# Magnetorquer_Board.net
KiCad netlist of a schematic drawn in EAGLE
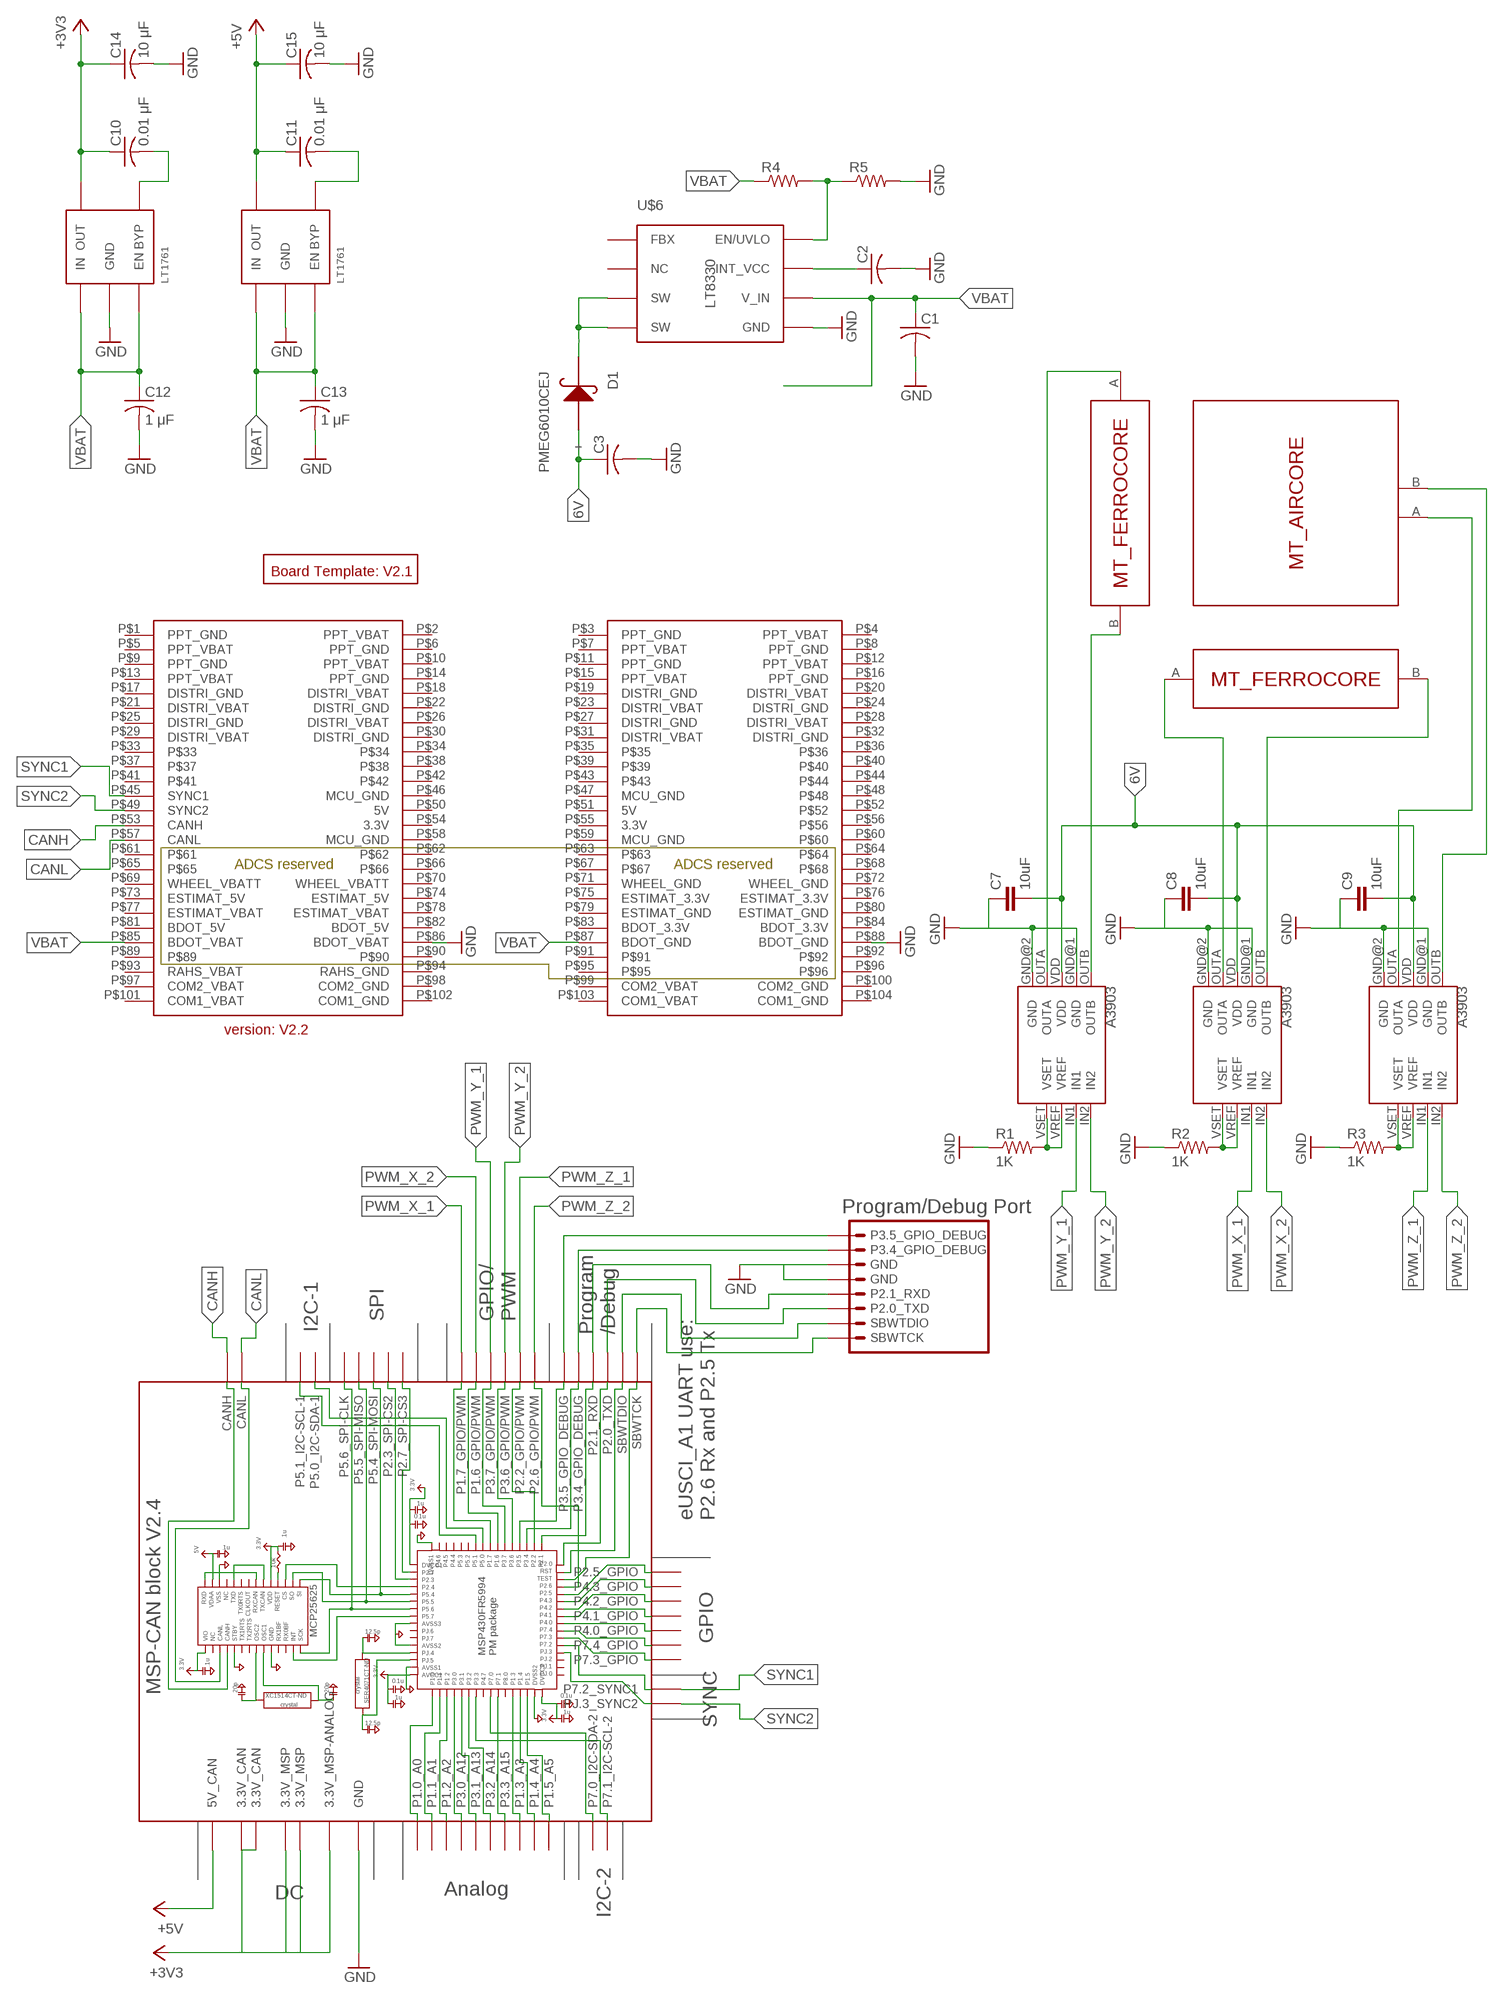
[diagram p0: schematic, sheet 1]

(export (version "E")
  (design (tool "Eeschema 10.0.6"))
  (components
    (comp (ref "C1")
      (value "C-USC0805")
      (footprint "eagle-import:C0805")
      (libsource (lib "eagle-import") (part "C-USC0805"))
    )
    (comp (ref "C2")
      (value "C-USC0805")
      (footprint "eagle-import:C0805")
      (libsource (lib "eagle-import") (part "C-USC0805"))
    )
    (comp (ref "C3")
      (value "C-USC0805")
      (footprint "eagle-import:C0805")
      (libsource (lib "eagle-import") (part "C-USC0805"))
    )
    (comp (ref "C7")
      (value "10uF")
      (footprint "eagle-import:C0805")
      (libsource (lib "eagle-import") (part "C-EUC0805"))
    )
    (comp (ref "C8")
      (value "10uF")
      (footprint "eagle-import:C0805")
      (libsource (lib "eagle-import") (part "C-EUC0805"))
    )
    (comp (ref "C9")
      (value "10uF")
      (footprint "eagle-import:C0805")
      (libsource (lib "eagle-import") (part "C-EUC0805"))
    )
    (comp (ref "C10")
      (value "0.01 μF")
      (footprint "eagle-import:C0805")
      (libsource (lib "eagle-import") (part "C-USC0805"))
    )
    (comp (ref "C11")
      (value "0.01 μF")
      (footprint "eagle-import:C0805")
      (libsource (lib "eagle-import") (part "C-USC0805"))
    )
    (comp (ref "C12")
      (value "1 μF")
      (footprint "eagle-import:C0805")
      (libsource (lib "eagle-import") (part "C-USC0805"))
    )
    (comp (ref "C13")
      (value "1 μF")
      (footprint "eagle-import:C0805")
      (libsource (lib "eagle-import") (part "C-USC0805"))
    )
    (comp (ref "C14")
      (value "10 μF")
      (footprint "eagle-import:C0805")
      (libsource (lib "eagle-import") (part "C-USC0805"))
    )
    (comp (ref "C15")
      (value "10 μF")
      (footprint "eagle-import:C0805")
      (libsource (lib "eagle-import") (part "C-USC0805"))
    )
    (comp (ref "D1")
      (value "PMEG6010CEJ")
      (footprint "eagle-import:SC-90")
      (libsource (lib "eagle-import") (part "PMEG6010CEJ"))
    )
    (comp (ref "LDO_3V3")
      (value "LINEAR_LDO_LT1761-X")
      (footprint "eagle-import:SOT-23-5")
      (libsource (lib "eagle-import") (part "LINEAR_LDO_LT1761-X"))
    )
    (comp (ref "LDO_5V")
      (value "LINEAR_LDO_LT1761-X")
      (footprint "eagle-import:SOT-23-5")
      (libsource (lib "eagle-import") (part "LINEAR_LDO_LT1761-X"))
    )
    (comp (ref "R1")
      (value "1K")
      (footprint "eagle-import:R0603")
      (libsource (lib "eagle-import") (part "R-US_R0603"))
    )
    (comp (ref "R2")
      (value "1K")
      (footprint "eagle-import:R0603")
      (libsource (lib "eagle-import") (part "R-US_R0603"))
    )
    (comp (ref "R3")
      (value "1K")
      (footprint "eagle-import:R0603")
      (libsource (lib "eagle-import") (part "R-US_R0603"))
    )
    (comp (ref "R4")
      (value "R-US_R0805")
      (footprint "eagle-import:R0805")
      (libsource (lib "eagle-import") (part "R-US_R0805"))
    )
    (comp (ref "R5")
      (value "R-US_R0805")
      (footprint "eagle-import:R0805")
      (libsource (lib "eagle-import") (part "R-US_R0805"))
    )
    (comp (ref "U$1")
      (value "PC104_CONNECTOR")
      (footprint "eagle-import:PC104_CONNECTOR")
      (libsource (lib "eagle-import") (part "PC104_CONNECTOR"))
    )
    (comp (ref "U$2")
      (value "BOARD_TEMPLATE")
      (footprint "eagle-import:BOARD_TEMPLATE")
      (libsource (lib "eagle-import") (part "BOARD_TEMPLATE"))
    )
    (comp (ref "U$3")
      (value "MT_AIRCORE")
      (footprint "eagle-import:MT_AIRCORE")
      (libsource (lib "eagle-import") (part "MT_AIRCORE"))
    )
    (comp (ref "U$4")
      (value "MT_FERROCORE")
      (footprint "eagle-import:MT_FERROCORE")
      (libsource (lib "eagle-import") (part "MT_FERROCORE"))
    )
    (comp (ref "U$5")
      (value "MT_FERROCORE")
      (footprint "eagle-import:MT_FERROCORE")
      (libsource (lib "eagle-import") (part "MT_FERROCORE"))
    )
    (comp (ref "U$6")
      (value "LT8330")
      (footprint "eagle-import:DDB")
      (libsource (lib "eagle-import") (part "LT8330"))
    )
    (comp (ref "U$7")
      (value "MSP-CAN_BLOCK")
      (footprint "eagle-import:MSP-CAN_BLOCK")
      (libsource (lib "eagle-import") (part "MSP-CAN_BLOCK"))
    )
    (comp (ref "U$8")
      (value "PROGRAM/DEBUG_PORT")
      (footprint "eagle-import:1X08_CONNECTOR")
      (libsource (lib "eagle-import") (part "PROGRAM/DEBUG_PORT"))
    )
    (comp (ref "U1")
      (value "A3903")
      (footprint "eagle-import:DFN-8EE")
      (libsource (lib "eagle-import") (part "A3903"))
    )
    (comp (ref "U2")
      (value "A3903")
      (footprint "eagle-import:DFN-8EE")
      (libsource (lib "eagle-import") (part "A3903"))
    )
    (comp (ref "U3")
      (value "A3903")
      (footprint "eagle-import:DFN-8EE")
      (libsource (lib "eagle-import") (part "A3903"))
    )
  )
  (nets
    (net (code "1") (name "+3V3") (class "Default")
      (node (ref "C10") (pin "1") (pinfunction "1_1") (pintype "passive"))
      (node (ref "C14") (pin "1") (pinfunction "1_1") (pintype "passive"))
      (node (ref "LDO_3V3") (pin "P$5") (pinfunction "OUT_P$5") (pintype "bidirectional"))
      (node (ref "U$7") (pin "3.3V@CAN1") (pinfunction "3.3V_CAN_3.3V@CAN1") (pintype "bidirectional"))
      (node (ref "U$7") (pin "3.3V@CAN2") (pinfunction "3.3V_CAN_3.3V@CAN2") (pintype "bidirectional"))
      (node (ref "U$7") (pin "3.3V@MSP1") (pinfunction "3.3V_MSP_3.3V@MSP1") (pintype "bidirectional"))
      (node (ref "U$7") (pin "3.3V@MSP2") (pinfunction "3.3V_MSP_3.3V@MSP2") (pintype "bidirectional"))
      (node (ref "U$7") (pin "3.3V_ANALOG@MSP2") (pinfunction "3.3V_MSP-ANALOG_3.3V_ANALOG@MSP2") (pintype "bidirectional"))
    )
    (net (code "2") (name "+5V") (class "Default")
      (node (ref "C11") (pin "1") (pinfunction "1_1") (pintype "passive"))
      (node (ref "C15") (pin "1") (pinfunction "1_1") (pintype "passive"))
      (node (ref "LDO_5V") (pin "P$5") (pinfunction "OUT_P$5") (pintype "bidirectional"))
      (node (ref "U$7") (pin "5V") (pinfunction "5V_CAN_5V") (pintype "bidirectional"))
    )
    (net (code "3") (name "6V") (class "Default")
      (node (ref "C3") (pin "1") (pinfunction "1_1") (pintype "passive"))
      (node (ref "C7") (pin "2") (pinfunction "2_2") (pintype "passive"))
      (node (ref "C8") (pin "2") (pinfunction "2_2") (pintype "passive"))
      (node (ref "C9") (pin "2") (pinfunction "2_2") (pintype "passive"))
      (node (ref "D1") (pin "P$1") (pinfunction "+_P$1") (pintype "bidirectional"))
      (node (ref "U1") (pin "VDD") (pinfunction "VDD_VDD") (pintype "power_in"))
      (node (ref "U2") (pin "VDD") (pinfunction "VDD_VDD") (pintype "power_in"))
      (node (ref "U3") (pin "VDD") (pinfunction "VDD_VDD") (pintype "power_in"))
    )
    (net (code "4") (name "CANH") (class "Default")
      (node (ref "U$1") (pin "P$53") (pinfunction "CANH_P$53") (pintype "bidirectional"))
      (node (ref "U$7") (pin "CANH") (pinfunction "CANH_CANH") (pintype "bidirectional"))
    )
    (net (code "5") (name "CANL") (class "Default")
      (node (ref "U$1") (pin "P$57") (pinfunction "CANL_P$57") (pintype "bidirectional"))
      (node (ref "U$7") (pin "CANL") (pinfunction "CANL_CANL") (pintype "bidirectional"))
    )
    (net (code "6") (name "GND") (class "Default")
      (node (ref "C1") (pin "2") (pinfunction "2_2") (pintype "passive"))
      (node (ref "C12") (pin "2") (pinfunction "2_2") (pintype "passive"))
      (node (ref "C13") (pin "2") (pinfunction "2_2") (pintype "passive"))
      (node (ref "C14") (pin "2") (pinfunction "2_2") (pintype "passive"))
      (node (ref "C15") (pin "2") (pinfunction "2_2") (pintype "passive"))
      (node (ref "C2") (pin "2") (pinfunction "2_2") (pintype "passive"))
      (node (ref "C3") (pin "2") (pinfunction "2_2") (pintype "passive"))
      (node (ref "C7") (pin "1") (pinfunction "1_1") (pintype "passive"))
      (node (ref "C8") (pin "1") (pinfunction "1_1") (pintype "passive"))
      (node (ref "C9") (pin "1") (pinfunction "1_1") (pintype "passive"))
      (node (ref "LDO_3V3") (pin "P$2") (pinfunction "GND_P$2") (pintype "bidirectional"))
      (node (ref "LDO_5V") (pin "P$2") (pinfunction "GND_P$2") (pintype "bidirectional"))
      (node (ref "R1") (pin "1") (pinfunction "1_1") (pintype "passive"))
      (node (ref "R2") (pin "1") (pinfunction "1_1") (pintype "passive"))
      (node (ref "R3") (pin "1") (pinfunction "1_1") (pintype "passive"))
      (node (ref "R5") (pin "2") (pinfunction "2_2") (pintype "passive"))
      (node (ref "U$1") (pin "P$86") (pinfunction "BDOT_VBAT_P$86") (pintype "bidirectional"))
      (node (ref "U$1") (pin "P$88") (pinfunction "BDOT_GND_P$88") (pintype "bidirectional"))
      (node (ref "U$6") (pin "GND") (pinfunction "GND_GND") (pintype "bidirectional"))
      (node (ref "U$6") (pin "P$5") (pinfunction "GND_P$5") (pintype "bidirectional"))
      (node (ref "U$7") (pin "GND@1") (pinfunction "GND_GND@1") (pintype "bidirectional"))
      (node (ref "U$7") (pin "GND@10") (pinfunction "GND_GND@10") (pintype "bidirectional"))
      (node (ref "U$7") (pin "GND@11") (pinfunction "GND_GND@11") (pintype "bidirectional"))
      (node (ref "U$7") (pin "GND@12") (pinfunction "GND_GND@12") (pintype "bidirectional"))
      (node (ref "U$7") (pin "GND@13") (pinfunction "GND_GND@13") (pintype "bidirectional"))
      (node (ref "U$7") (pin "GND@14") (pinfunction "GND_GND@14") (pintype "bidirectional"))
      (node (ref "U$7") (pin "GND@15") (pinfunction "GND_GND@15") (pintype "bidirectional"))
      (node (ref "U$7") (pin "GND@16") (pinfunction "GND_GND@16") (pintype "bidirectional"))
      (node (ref "U$7") (pin "GND@17") (pinfunction "GND_GND@17") (pintype "bidirectional"))
      (node (ref "U$7") (pin "GND@2") (pinfunction "GND_GND@2") (pintype "bidirectional"))
      (node (ref "U$7") (pin "GND@26") (pinfunction "GND_GND@26") (pintype "bidirectional"))
      (node (ref "U$7") (pin "GND@3") (pinfunction "GND_GND@3") (pintype "bidirectional"))
      (node (ref "U$7") (pin "GND@4") (pinfunction "GND_GND@4") (pintype "bidirectional"))
      (node (ref "U$7") (pin "GND@5") (pinfunction "GND_GND@5") (pintype "bidirectional"))
      (node (ref "U$7") (pin "GND@7") (pinfunction "GND_GND@7") (pintype "bidirectional"))
      (node (ref "U$7") (pin "GND@8") (pinfunction "GND_GND@8") (pintype "bidirectional"))
      (node (ref "U$7") (pin "GND@9") (pinfunction "GND_GND@9") (pintype "bidirectional"))
      (node (ref "U$8") (pin "5") (pinfunction "GND_5") (pintype "bidirectional"))
      (node (ref "U$8") (pin "6") (pinfunction "GND_6") (pintype "bidirectional"))
      (node (ref "U1") (pin "GND@1") (pinfunction "GND_GND@1") (pintype "power_in"))
      (node (ref "U1") (pin "GND@2") (pinfunction "GND_GND@2") (pintype "power_in"))
      (node (ref "U2") (pin "GND@1") (pinfunction "GND_GND@1") (pintype "power_in"))
      (node (ref "U2") (pin "GND@2") (pinfunction "GND_GND@2") (pintype "power_in"))
      (node (ref "U3") (pin "GND@1") (pinfunction "GND_GND@1") (pintype "power_in"))
      (node (ref "U3") (pin "GND@2") (pinfunction "GND_GND@2") (pintype "power_in"))
    )
    (net (code "7") (name "Net-(D1--)") (class "Default")
      (node (ref "D1") (pin "P$2") (pinfunction "-_P$2") (pintype "bidirectional"))
      (node (ref "U$6") (pin "P$3") (pinfunction "SW_P$3") (pintype "bidirectional"))
      (node (ref "U$6") (pin "P$4") (pinfunction "SW_P$4") (pintype "bidirectional"))
    )
    (net (code "8") (name "Net-(LDO_3V3-BYP)") (class "Default")
      (node (ref "C10") (pin "2") (pinfunction "2_2") (pintype "passive"))
      (node (ref "LDO_3V3") (pin "P$4") (pinfunction "BYP_P$4") (pintype "bidirectional"))
    )
    (net (code "9") (name "Net-(LDO_5V-BYP)") (class "Default")
      (node (ref "C11") (pin "2") (pinfunction "2_2") (pintype "passive"))
      (node (ref "LDO_5V") (pin "P$4") (pinfunction "BYP_P$4") (pintype "bidirectional"))
    )
    (net (code "10") (name "Net-(R1-Pad2)") (class "Default")
      (node (ref "R1") (pin "2") (pinfunction "2_2") (pintype "passive"))
      (node (ref "U1") (pin "VREF") (pinfunction "VREF_VREF") (pintype "power_in"))
      (node (ref "U1") (pin "VSET") (pinfunction "VSET_VSET") (pintype "bidirectional"))
    )
    (net (code "11") (name "Net-(R2-Pad2)") (class "Default")
      (node (ref "R2") (pin "2") (pinfunction "2_2") (pintype "passive"))
      (node (ref "U2") (pin "VREF") (pinfunction "VREF_VREF") (pintype "power_in"))
      (node (ref "U2") (pin "VSET") (pinfunction "VSET_VSET") (pintype "bidirectional"))
    )
    (net (code "12") (name "Net-(R3-Pad2)") (class "Default")
      (node (ref "R3") (pin "2") (pinfunction "2_2") (pintype "passive"))
      (node (ref "U3") (pin "VREF") (pinfunction "VREF_VREF") (pintype "power_in"))
      (node (ref "U3") (pin "VSET") (pinfunction "VSET_VSET") (pintype "bidirectional"))
    )
    (net (code "13") (name "Net-(U$3-PadA)") (class "Default")
      (node (ref "U$3") (pin "A") (pinfunction "A_A") (pintype "bidirectional"))
      (node (ref "U3") (pin "OUTA") (pinfunction "OUTA_OUTA") (pintype "output"))
    )
    (net (code "14") (name "Net-(U$3-PadB)") (class "Default")
      (node (ref "U$3") (pin "B") (pinfunction "B_B") (pintype "bidirectional"))
      (node (ref "U3") (pin "OUTB") (pinfunction "OUTB_OUTB") (pintype "output"))
    )
    (net (code "15") (name "Net-(U$4-PadA)") (class "Default")
      (node (ref "U$4") (pin "A") (pinfunction "A_A") (pintype "bidirectional"))
      (node (ref "U1") (pin "OUTA") (pinfunction "OUTA_OUTA") (pintype "output"))
    )
    (net (code "16") (name "Net-(U$4-PadB)") (class "Default")
      (node (ref "U$4") (pin "B") (pinfunction "B_B") (pintype "bidirectional"))
      (node (ref "U1") (pin "OUTB") (pinfunction "OUTB_OUTB") (pintype "output"))
    )
    (net (code "17") (name "Net-(U$5-PadA)") (class "Default")
      (node (ref "U$5") (pin "A") (pinfunction "A_A") (pintype "bidirectional"))
      (node (ref "U2") (pin "OUTA") (pinfunction "OUTA_OUTA") (pintype "output"))
    )
    (net (code "18") (name "Net-(U$5-PadB)") (class "Default")
      (node (ref "U$5") (pin "B") (pinfunction "B_B") (pintype "bidirectional"))
      (node (ref "U2") (pin "OUTB") (pinfunction "OUTB_OUTB") (pintype "output"))
    )
    (net (code "19") (name "Net-(U$6-EN{slash}UVLO)") (class "Default")
      (node (ref "R4") (pin "2") (pinfunction "2_2") (pintype "passive"))
      (node (ref "R5") (pin "1") (pinfunction "1_1") (pintype "passive"))
      (node (ref "U$6") (pin "P$8") (pinfunction "EN/UVLO_P$8") (pintype "bidirectional"))
    )
    (net (code "20") (name "Net-(U$6-INT_VCC)") (class "Default")
      (node (ref "C2") (pin "1") (pinfunction "1_1") (pintype "passive"))
      (node (ref "U$6") (pin "P$7") (pinfunction "INT_VCC_P$7") (pintype "bidirectional"))
    )
    (net (code "21") (name "Net-(U$7-PadSBWTCK)") (class "Default")
      (node (ref "U$7") (pin "SBWTCK") (pinfunction "SBWTCK_SBWTCK") (pintype "bidirectional"))
      (node (ref "U$8") (pin "SBWTCK") (pinfunction "SBWTCK_SBWTCK") (pintype "bidirectional"))
    )
    (net (code "22") (name "Net-(U$8-P2.0_TXD)") (class "Default")
      (node (ref "U$7") (pin "P2.0_TXD") (pinfunction "P2.0_TXD_P2.0_TXD") (pintype "bidirectional"))
      (node (ref "U$8") (pin "3") (pinfunction "P2.0_TXD_3") (pintype "bidirectional"))
    )
    (net (code "23") (name "Net-(U$8-P2.1_RXD)") (class "Default")
      (node (ref "U$7") (pin "P2.1_RXD") (pinfunction "P2.1_RXD_P2.1_RXD") (pintype "bidirectional"))
      (node (ref "U$8") (pin "4") (pinfunction "P2.1_RXD_4") (pintype "bidirectional"))
    )
    (net (code "24") (name "Net-(U$8-P3.4_GPIO_DEBUG)") (class "Default")
      (node (ref "U$7") (pin "P3.4_GPIO_DEBUG") (pinfunction "P3.4_GPIO_DEBUG_P3.4_GPIO_DEBUG") (pintype "bidirectional"))
      (node (ref "U$8") (pin "7") (pinfunction "P3.4_GPIO_DEBUG_7") (pintype "bidirectional"))
    )
    (net (code "25") (name "Net-(U$8-P3.5_GPIO_DEBUG)") (class "Default")
      (node (ref "U$7") (pin "P3.5_GPIO_DEBUG") (pinfunction "P3.5_GPIO_DEBUG_P3.5_GPIO_DEBUG") (pintype "bidirectional"))
      (node (ref "U$8") (pin "8") (pinfunction "P3.5_GPIO_DEBUG_8") (pintype "bidirectional"))
    )
    (net (code "26") (name "Net-(U$8-SBWTDIO)") (class "Default")
      (node (ref "U$7") (pin "SBWTDIO") (pinfunction "SBWTDIO_SBWTDIO") (pintype "bidirectional"))
      (node (ref "U$8") (pin "2") (pinfunction "SBWTDIO_2") (pintype "bidirectional"))
    )
    (net (code "27") (name "PWM_X_1") (class "Default")
      (node (ref "U$7") (pin "P1.7_GPIO/PWM") (pinfunction "P1.7_GPIO/PWM_P1.7_GPIO/PWM") (pintype "bidirectional"))
      (node (ref "U2") (pin "IN1") (pinfunction "IN1_IN1") (pintype "input"))
    )
    (net (code "28") (name "PWM_X_2") (class "Default")
      (node (ref "U$7") (pin "P1.6_GPIO/PWM") (pinfunction "P1.6_GPIO/PWM_P1.6_GPIO/PWM") (pintype "bidirectional"))
      (node (ref "U2") (pin "IN2") (pinfunction "IN2_IN2") (pintype "input"))
    )
    (net (code "29") (name "PWM_Y_1") (class "Default")
      (node (ref "U$7") (pin "P3.7_GPIO/PWM") (pinfunction "P3.7_GPIO/PWM_P3.7_GPIO/PWM") (pintype "bidirectional"))
      (node (ref "U1") (pin "IN1") (pinfunction "IN1_IN1") (pintype "input"))
    )
    (net (code "30") (name "PWM_Y_2") (class "Default")
      (node (ref "U$7") (pin "P3.6_GPIO/PWM") (pinfunction "P3.6_GPIO/PWM_P3.6_GPIO/PWM") (pintype "bidirectional"))
      (node (ref "U1") (pin "IN2") (pinfunction "IN2_IN2") (pintype "input"))
    )
    (net (code "31") (name "PWM_Z_1") (class "Default")
      (node (ref "U$7") (pin "P2.2_GPIO/PWM") (pinfunction "P2.2_GPIO/PWM_P2.2_GPIO/PWM") (pintype "bidirectional"))
      (node (ref "U3") (pin "IN1") (pinfunction "IN1_IN1") (pintype "input"))
    )
    (net (code "32") (name "PWM_Z_2") (class "Default")
      (node (ref "U$7") (pin "P2.6_GPIO/PWM") (pinfunction "P2.6_GPIO/PWM_P2.6_GPIO/PWM") (pintype "bidirectional"))
      (node (ref "U3") (pin "IN2") (pinfunction "IN2_IN2") (pintype "input"))
    )
    (net (code "33") (name "SYNC1") (class "Default")
      (node (ref "U$1") (pin "P$45") (pinfunction "SYNC1_P$45") (pintype "bidirectional"))
      (node (ref "U$7") (pin "P7.2_SYNC1") (pinfunction "P7.2_SYNC1_P7.2_SYNC1") (pintype "bidirectional"))
    )
    (net (code "34") (name "SYNC2") (class "Default")
      (node (ref "U$1") (pin "P$49") (pinfunction "SYNC2_P$49") (pintype "bidirectional"))
      (node (ref "U$7") (pin "PJ.3_SYNC2") (pinfunction "PJ.3_SYNC2_PJ.3_SYNC2") (pintype "bidirectional"))
    )
    (net (code "35") (name "VBAT") (class "Default")
      (node (ref "C1") (pin "1") (pinfunction "1_1") (pintype "passive"))
      (node (ref "C12") (pin "1") (pinfunction "1_1") (pintype "passive"))
      (node (ref "C13") (pin "1") (pinfunction "1_1") (pintype "passive"))
      (node (ref "LDO_3V3") (pin "P$1") (pinfunction "IN_P$1") (pintype "bidirectional"))
      (node (ref "LDO_3V3") (pin "P$3") (pinfunction "EN_P$3") (pintype "bidirectional"))
      (node (ref "LDO_5V") (pin "P$1") (pinfunction "IN_P$1") (pintype "bidirectional"))
      (node (ref "LDO_5V") (pin "P$3") (pinfunction "EN_P$3") (pintype "bidirectional"))
      (node (ref "R4") (pin "1") (pinfunction "1_1") (pintype "passive"))
      (node (ref "U$1") (pin "P$85") (pinfunction "BDOT_VBAT_P$85") (pintype "bidirectional"))
      (node (ref "U$1") (pin "P$87") (pinfunction "BDOT_GND_P$87") (pintype "bidirectional"))
      (node (ref "U$6") (pin "P$6") (pinfunction "V_IN_P$6") (pintype "bidirectional"))
    )
    (net (code "36") (name "unconnected-(U$1-3.3V-PadP$54)") (class "Default")
      (node (ref "U$1") (pin "P$54") (pinfunction "3.3V_P$54") (pintype "bidirectional"))
    )
    (net (code "37") (name "unconnected-(U$1-3.3V-PadP$55)") (class "Default")
      (node (ref "U$1") (pin "P$55") (pinfunction "3.3V_P$55") (pintype "bidirectional"))
    )
    (net (code "38") (name "unconnected-(U$1-5V-PadP$50)") (class "Default")
      (node (ref "U$1") (pin "P$50") (pinfunction "5V_P$50") (pintype "bidirectional"))
    )
    (net (code "39") (name "unconnected-(U$1-5V-PadP$51)") (class "Default")
      (node (ref "U$1") (pin "P$51") (pinfunction "5V_P$51") (pintype "bidirectional"))
    )
    (net (code "40") (name "unconnected-(U$1-BDOT_3.3V-PadP$83)") (class "Default")
      (node (ref "U$1") (pin "P$83") (pinfunction "BDOT_3.3V_P$83") (pintype "bidirectional"))
    )
    (net (code "41") (name "unconnected-(U$1-BDOT_3.3V-PadP$84)") (class "Default")
      (node (ref "U$1") (pin "P$84") (pinfunction "BDOT_3.3V_P$84") (pintype "bidirectional"))
    )
    (net (code "42") (name "unconnected-(U$1-BDOT_5V-PadP$81)") (class "Default")
      (node (ref "U$1") (pin "P$81") (pinfunction "BDOT_5V_P$81") (pintype "bidirectional"))
    )
    (net (code "43") (name "unconnected-(U$1-BDOT_5V-PadP$82)") (class "Default")
      (node (ref "U$1") (pin "P$82") (pinfunction "BDOT_5V_P$82") (pintype "bidirectional"))
    )
    (net (code "44") (name "unconnected-(U$1-COM1_GND-PadP$102)") (class "Default")
      (node (ref "U$1") (pin "P$102") (pinfunction "COM1_GND_P$102") (pintype "bidirectional"))
    )
    (net (code "45") (name "unconnected-(U$1-COM1_GND-PadP$104)") (class "Default")
      (node (ref "U$1") (pin "P$104") (pinfunction "COM1_GND_P$104") (pintype "bidirectional"))
    )
    (net (code "46") (name "unconnected-(U$1-COM1_VBAT-PadP$101)") (class "Default")
      (node (ref "U$1") (pin "P$101") (pinfunction "COM1_VBAT_P$101") (pintype "bidirectional"))
    )
    (net (code "47") (name "unconnected-(U$1-COM1_VBAT-PadP$103)") (class "Default")
      (node (ref "U$1") (pin "P$103") (pinfunction "COM1_VBAT_P$103") (pintype "bidirectional"))
    )
    (net (code "48") (name "unconnected-(U$1-COM2_GND-PadP$98)") (class "Default")
      (node (ref "U$1") (pin "P$98") (pinfunction "COM2_GND_P$98") (pintype "bidirectional"))
    )
    (net (code "49") (name "unconnected-(U$1-COM2_GND-PadP$100)") (class "Default")
      (node (ref "U$1") (pin "P$100") (pinfunction "COM2_GND_P$100") (pintype "bidirectional"))
    )
    (net (code "50") (name "unconnected-(U$1-COM2_VBAT-PadP$97)") (class "Default")
      (node (ref "U$1") (pin "P$97") (pinfunction "COM2_VBAT_P$97") (pintype "bidirectional"))
    )
    (net (code "51") (name "unconnected-(U$1-COM2_VBAT-PadP$99)") (class "Default")
      (node (ref "U$1") (pin "P$99") (pinfunction "COM2_VBAT_P$99") (pintype "bidirectional"))
    )
    (net (code "52") (name "unconnected-(U$1-DISTRI_GND-PadP$17)") (class "Default")
      (node (ref "U$1") (pin "P$17") (pinfunction "DISTRI_GND_P$17") (pintype "bidirectional"))
    )
    (net (code "53") (name "unconnected-(U$1-DISTRI_GND-PadP$19)") (class "Default")
      (node (ref "U$1") (pin "P$19") (pinfunction "DISTRI_GND_P$19") (pintype "bidirectional"))
    )
    (net (code "54") (name "unconnected-(U$1-DISTRI_GND-PadP$22)") (class "Default")
      (node (ref "U$1") (pin "P$22") (pinfunction "DISTRI_GND_P$22") (pintype "bidirectional"))
    )
    (net (code "55") (name "unconnected-(U$1-DISTRI_GND-PadP$24)") (class "Default")
      (node (ref "U$1") (pin "P$24") (pinfunction "DISTRI_GND_P$24") (pintype "bidirectional"))
    )
    (net (code "56") (name "unconnected-(U$1-DISTRI_GND-PadP$25)") (class "Default")
      (node (ref "U$1") (pin "P$25") (pinfunction "DISTRI_GND_P$25") (pintype "bidirectional"))
    )
    (net (code "57") (name "unconnected-(U$1-DISTRI_GND-PadP$27)") (class "Default")
      (node (ref "U$1") (pin "P$27") (pinfunction "DISTRI_GND_P$27") (pintype "bidirectional"))
    )
    (net (code "58") (name "unconnected-(U$1-DISTRI_GND-PadP$30)") (class "Default")
      (node (ref "U$1") (pin "P$30") (pinfunction "DISTRI_GND_P$30") (pintype "bidirectional"))
    )
    (net (code "59") (name "unconnected-(U$1-DISTRI_GND-PadP$32)") (class "Default")
      (node (ref "U$1") (pin "P$32") (pinfunction "DISTRI_GND_P$32") (pintype "bidirectional"))
    )
    (net (code "60") (name "unconnected-(U$1-DISTRI_VBAT-PadP$18)") (class "Default")
      (node (ref "U$1") (pin "P$18") (pinfunction "DISTRI_VBAT_P$18") (pintype "bidirectional"))
    )
    (net (code "61") (name "unconnected-(U$1-DISTRI_VBAT-PadP$20)") (class "Default")
      (node (ref "U$1") (pin "P$20") (pinfunction "DISTRI_VBAT_P$20") (pintype "bidirectional"))
    )
    (net (code "62") (name "unconnected-(U$1-DISTRI_VBAT-PadP$21)") (class "Default")
      (node (ref "U$1") (pin "P$21") (pinfunction "DISTRI_VBAT_P$21") (pintype "bidirectional"))
    )
    (net (code "63") (name "unconnected-(U$1-DISTRI_VBAT-PadP$23)") (class "Default")
      (node (ref "U$1") (pin "P$23") (pinfunction "DISTRI_VBAT_P$23") (pintype "bidirectional"))
    )
    (net (code "64") (name "unconnected-(U$1-DISTRI_VBAT-PadP$26)") (class "Default")
      (node (ref "U$1") (pin "P$26") (pinfunction "DISTRI_VBAT_P$26") (pintype "bidirectional"))
    )
    (net (code "65") (name "unconnected-(U$1-DISTRI_VBAT-PadP$28)") (class "Default")
      (node (ref "U$1") (pin "P$28") (pinfunction "DISTRI_VBAT_P$28") (pintype "bidirectional"))
    )
    (net (code "66") (name "unconnected-(U$1-DISTRI_VBAT-PadP$29)") (class "Default")
      (node (ref "U$1") (pin "P$29") (pinfunction "DISTRI_VBAT_P$29") (pintype "bidirectional"))
    )
    (net (code "67") (name "unconnected-(U$1-DISTRI_VBAT-PadP$31)") (class "Default")
      (node (ref "U$1") (pin "P$31") (pinfunction "DISTRI_VBAT_P$31") (pintype "bidirectional"))
    )
    (net (code "68") (name "unconnected-(U$1-ESTIMAT_3.3V-PadP$75)") (class "Default")
      (node (ref "U$1") (pin "P$75") (pinfunction "ESTIMAT_3.3V_P$75") (pintype "bidirectional"))
    )
    (net (code "69") (name "unconnected-(U$1-ESTIMAT_3.3V-PadP$76)") (class "Default")
      (node (ref "U$1") (pin "P$76") (pinfunction "ESTIMAT_3.3V_P$76") (pintype "bidirectional"))
    )
    (net (code "70") (name "unconnected-(U$1-ESTIMAT_5V-PadP$73)") (class "Default")
      (node (ref "U$1") (pin "P$73") (pinfunction "ESTIMAT_5V_P$73") (pintype "bidirectional"))
    )
    (net (code "71") (name "unconnected-(U$1-ESTIMAT_5V-PadP$74)") (class "Default")
      (node (ref "U$1") (pin "P$74") (pinfunction "ESTIMAT_5V_P$74") (pintype "bidirectional"))
    )
    (net (code "72") (name "unconnected-(U$1-ESTIMAT_GND-PadP$79)") (class "Default")
      (node (ref "U$1") (pin "P$79") (pinfunction "ESTIMAT_GND_P$79") (pintype "bidirectional"))
    )
    (net (code "73") (name "unconnected-(U$1-ESTIMAT_GND-PadP$80)") (class "Default")
      (node (ref "U$1") (pin "P$80") (pinfunction "ESTIMAT_GND_P$80") (pintype "bidirectional"))
    )
    (net (code "74") (name "unconnected-(U$1-ESTIMAT_VBAT-PadP$77)") (class "Default")
      (node (ref "U$1") (pin "P$77") (pinfunction "ESTIMAT_VBAT_P$77") (pintype "bidirectional"))
    )
    (net (code "75") (name "unconnected-(U$1-ESTIMAT_VBAT-PadP$78)") (class "Default")
      (node (ref "U$1") (pin "P$78") (pinfunction "ESTIMAT_VBAT_P$78") (pintype "bidirectional"))
    )
    (net (code "76") (name "unconnected-(U$1-MCU_GND-PadP$46)") (class "Default")
      (node (ref "U$1") (pin "P$46") (pinfunction "MCU_GND_P$46") (pintype "bidirectional"))
    )
    (net (code "77") (name "unconnected-(U$1-MCU_GND-PadP$47)") (class "Default")
      (node (ref "U$1") (pin "P$47") (pinfunction "MCU_GND_P$47") (pintype "bidirectional"))
    )
    (net (code "78") (name "unconnected-(U$1-MCU_GND-PadP$58)") (class "Default")
      (node (ref "U$1") (pin "P$58") (pinfunction "MCU_GND_P$58") (pintype "bidirectional"))
    )
    (net (code "79") (name "unconnected-(U$1-MCU_GND-PadP$59)") (class "Default")
      (node (ref "U$1") (pin "P$59") (pinfunction "MCU_GND_P$59") (pintype "bidirectional"))
    )
    (net (code "80") (name "unconnected-(U$1-PPT_GND-PadP$1)") (class "Default")
      (node (ref "U$1") (pin "P$1") (pinfunction "PPT_GND_P$1") (pintype "bidirectional"))
    )
    (net (code "81") (name "unconnected-(U$1-PPT_GND-PadP$3)") (class "Default")
      (node (ref "U$1") (pin "P$3") (pinfunction "PPT_GND_P$3") (pintype "bidirectional"))
    )
    (net (code "82") (name "unconnected-(U$1-PPT_GND-PadP$6)") (class "Default")
      (node (ref "U$1") (pin "P$6") (pinfunction "PPT_GND_P$6") (pintype "bidirectional"))
    )
    (net (code "83") (name "unconnected-(U$1-PPT_GND-PadP$8)") (class "Default")
      (node (ref "U$1") (pin "P$8") (pinfunction "PPT_GND_P$8") (pintype "bidirectional"))
    )
    (net (code "84") (name "unconnected-(U$1-PPT_GND-PadP$9)") (class "Default")
      (node (ref "U$1") (pin "P$9") (pinfunction "PPT_GND_P$9") (pintype "bidirectional"))
    )
    (net (code "85") (name "unconnected-(U$1-PPT_GND-PadP$11)") (class "Default")
      (node (ref "U$1") (pin "P$11") (pinfunction "PPT_GND_P$11") (pintype "bidirectional"))
    )
    (net (code "86") (name "unconnected-(U$1-PPT_GND-PadP$14)") (class "Default")
      (node (ref "U$1") (pin "P$14") (pinfunction "PPT_GND_P$14") (pintype "bidirectional"))
    )
    (net (code "87") (name "unconnected-(U$1-PPT_GND-PadP$16)") (class "Default")
      (node (ref "U$1") (pin "P$16") (pinfunction "PPT_GND_P$16") (pintype "bidirectional"))
    )
    (net (code "88") (name "unconnected-(U$1-PPT_VBAT-PadP$2)") (class "Default")
      (node (ref "U$1") (pin "P$2") (pinfunction "PPT_VBAT_P$2") (pintype "bidirectional"))
    )
    (net (code "89") (name "unconnected-(U$1-PPT_VBAT-PadP$4)") (class "Default")
      (node (ref "U$1") (pin "P$4") (pinfunction "PPT_VBAT_P$4") (pintype "bidirectional"))
    )
    (net (code "90") (name "unconnected-(U$1-PPT_VBAT-PadP$5)") (class "Default")
      (node (ref "U$1") (pin "P$5") (pinfunction "PPT_VBAT_P$5") (pintype "bidirectional"))
    )
    (net (code "91") (name "unconnected-(U$1-PPT_VBAT-PadP$7)") (class "Default")
      (node (ref "U$1") (pin "P$7") (pinfunction "PPT_VBAT_P$7") (pintype "bidirectional"))
    )
    (net (code "92") (name "unconnected-(U$1-PPT_VBAT-PadP$10)") (class "Default")
      (node (ref "U$1") (pin "P$10") (pinfunction "PPT_VBAT_P$10") (pintype "bidirectional"))
    )
    (net (code "93") (name "unconnected-(U$1-PPT_VBAT-PadP$12)") (class "Default")
      (node (ref "U$1") (pin "P$12") (pinfunction "PPT_VBAT_P$12") (pintype "bidirectional"))
    )
    (net (code "94") (name "unconnected-(U$1-PPT_VBAT-PadP$13)") (class "Default")
      (node (ref "U$1") (pin "P$13") (pinfunction "PPT_VBAT_P$13") (pintype "bidirectional"))
    )
    (net (code "95") (name "unconnected-(U$1-PPT_VBAT-PadP$15)") (class "Default")
      (node (ref "U$1") (pin "P$15") (pinfunction "PPT_VBAT_P$15") (pintype "bidirectional"))
    )
    (net (code "96") (name "unconnected-(U$1-PadP$33)") (class "Default")
      (node (ref "U$1") (pin "P$33") (pinfunction "P$33_P$33") (pintype "bidirectional"))
    )
    (net (code "97") (name "unconnected-(U$1-PadP$34)") (class "Default")
      (node (ref "U$1") (pin "P$34") (pinfunction "P$34_P$34") (pintype "bidirectional"))
    )
    (net (code "98") (name "unconnected-(U$1-PadP$35)") (class "Default")
      (node (ref "U$1") (pin "P$35") (pinfunction "P$35_P$35") (pintype "bidirectional"))
    )
    (net (code "99") (name "unconnected-(U$1-PadP$36)") (class "Default")
      (node (ref "U$1") (pin "P$36") (pinfunction "P$36_P$36") (pintype "bidirectional"))
    )
    (net (code "100") (name "unconnected-(U$1-PadP$37)") (class "Default")
      (node (ref "U$1") (pin "P$37") (pinfunction "P$37_P$37") (pintype "bidirectional"))
    )
    (net (code "101") (name "unconnected-(U$1-PadP$38)") (class "Default")
      (node (ref "U$1") (pin "P$38") (pinfunction "P$38_P$38") (pintype "bidirectional"))
    )
    (net (code "102") (name "unconnected-(U$1-PadP$39)") (class "Default")
      (node (ref "U$1") (pin "P$39") (pinfunction "P$39_P$39") (pintype "bidirectional"))
    )
    (net (code "103") (name "unconnected-(U$1-PadP$40)") (class "Default")
      (node (ref "U$1") (pin "P$40") (pinfunction "P$40_P$40") (pintype "bidirectional"))
    )
    (net (code "104") (name "unconnected-(U$1-PadP$41)") (class "Default")
      (node (ref "U$1") (pin "P$41") (pinfunction "P$41_P$41") (pintype "bidirectional"))
    )
    (net (code "105") (name "unconnected-(U$1-PadP$42)") (class "Default")
      (node (ref "U$1") (pin "P$42") (pinfunction "P$42_P$42") (pintype "bidirectional"))
    )
    (net (code "106") (name "unconnected-(U$1-PadP$43)") (class "Default")
      (node (ref "U$1") (pin "P$43") (pinfunction "P$43_P$43") (pintype "bidirectional"))
    )
    (net (code "107") (name "unconnected-(U$1-PadP$44)") (class "Default")
      (node (ref "U$1") (pin "P$44") (pinfunction "P$44_P$44") (pintype "bidirectional"))
    )
    (net (code "108") (name "unconnected-(U$1-PadP$48)") (class "Default")
      (node (ref "U$1") (pin "P$48") (pinfunction "P$48_P$48") (pintype "bidirectional"))
    )
    (net (code "109") (name "unconnected-(U$1-PadP$52)") (class "Default")
      (node (ref "U$1") (pin "P$52") (pinfunction "P$52_P$52") (pintype "bidirectional"))
    )
    (net (code "110") (name "unconnected-(U$1-PadP$56)") (class "Default")
      (node (ref "U$1") (pin "P$56") (pinfunction "P$56_P$56") (pintype "bidirectional"))
    )
    (net (code "111") (name "unconnected-(U$1-PadP$60)") (class "Default")
      (node (ref "U$1") (pin "P$60") (pinfunction "P$60_P$60") (pintype "bidirectional"))
    )
    (net (code "112") (name "unconnected-(U$1-PadP$61)") (class "Default")
      (node (ref "U$1") (pin "P$61") (pinfunction "P$61_P$61") (pintype "bidirectional"))
    )
    (net (code "113") (name "unconnected-(U$1-PadP$62)") (class "Default")
      (node (ref "U$1") (pin "P$62") (pinfunction "P$62_P$62") (pintype "bidirectional"))
    )
    (net (code "114") (name "unconnected-(U$1-PadP$63)") (class "Default")
      (node (ref "U$1") (pin "P$63") (pinfunction "P$63_P$63") (pintype "bidirectional"))
    )
    (net (code "115") (name "unconnected-(U$1-PadP$64)") (class "Default")
      (node (ref "U$1") (pin "P$64") (pinfunction "P$64_P$64") (pintype "bidirectional"))
    )
    (net (code "116") (name "unconnected-(U$1-PadP$65)") (class "Default")
      (node (ref "U$1") (pin "P$65") (pinfunction "P$65_P$65") (pintype "bidirectional"))
    )
    (net (code "117") (name "unconnected-(U$1-PadP$66)") (class "Default")
      (node (ref "U$1") (pin "P$66") (pinfunction "P$66_P$66") (pintype "bidirectional"))
    )
    (net (code "118") (name "unconnected-(U$1-PadP$67)") (class "Default")
      (node (ref "U$1") (pin "P$67") (pinfunction "P$67_P$67") (pintype "bidirectional"))
    )
    (net (code "119") (name "unconnected-(U$1-PadP$68)") (class "Default")
      (node (ref "U$1") (pin "P$68") (pinfunction "P$68_P$68") (pintype "bidirectional"))
    )
    (net (code "120") (name "unconnected-(U$1-PadP$89)") (class "Default")
      (node (ref "U$1") (pin "P$89") (pinfunction "P$89_P$89") (pintype "bidirectional"))
    )
    (net (code "121") (name "unconnected-(U$1-PadP$90)") (class "Default")
      (node (ref "U$1") (pin "P$90") (pinfunction "P$90_P$90") (pintype "bidirectional"))
    )
    (net (code "122") (name "unconnected-(U$1-PadP$91)") (class "Default")
      (node (ref "U$1") (pin "P$91") (pinfunction "P$91_P$91") (pintype "bidirectional"))
    )
    (net (code "123") (name "unconnected-(U$1-PadP$92)") (class "Default")
      (node (ref "U$1") (pin "P$92") (pinfunction "P$92_P$92") (pintype "bidirectional"))
    )
    (net (code "124") (name "unconnected-(U$1-PadP$95)") (class "Default")
      (node (ref "U$1") (pin "P$95") (pinfunction "P$95_P$95") (pintype "bidirectional"))
    )
    (net (code "125") (name "unconnected-(U$1-PadP$96)") (class "Default")
      (node (ref "U$1") (pin "P$96") (pinfunction "P$96_P$96") (pintype "bidirectional"))
    )
    (net (code "126") (name "unconnected-(U$1-RAHS_GND-PadP$94)") (class "Default")
      (node (ref "U$1") (pin "P$94") (pinfunction "RAHS_GND_P$94") (pintype "bidirectional"))
    )
    (net (code "127") (name "unconnected-(U$1-RAHS_VBAT-PadP$93)") (class "Default")
      (node (ref "U$1") (pin "P$93") (pinfunction "RAHS_VBAT_P$93") (pintype "bidirectional"))
    )
    (net (code "128") (name "unconnected-(U$1-WHEEL_GND-PadP$71)") (class "Default")
      (node (ref "U$1") (pin "P$71") (pinfunction "WHEEL_GND_P$71") (pintype "bidirectional"))
    )
    (net (code "129") (name "unconnected-(U$1-WHEEL_GND-PadP$72)") (class "Default")
      (node (ref "U$1") (pin "P$72") (pinfunction "WHEEL_GND_P$72") (pintype "bidirectional"))
    )
    (net (code "130") (name "unconnected-(U$1-WHEEL_VBATT-PadP$69)") (class "Default")
      (node (ref "U$1") (pin "P$69") (pinfunction "WHEEL_VBATT_P$69") (pintype "bidirectional"))
    )
    (net (code "131") (name "unconnected-(U$1-WHEEL_VBATT-PadP$70)") (class "Default")
      (node (ref "U$1") (pin "P$70") (pinfunction "WHEEL_VBATT_P$70") (pintype "bidirectional"))
    )
    (net (code "132") (name "unconnected-(U$6-FBX-PadP$1)") (class "Default")
      (node (ref "U$6") (pin "P$1") (pinfunction "FBX_P$1") (pintype "bidirectional"))
    )
    (net (code "133") (name "unconnected-(U$6-NC-PadP$2)") (class "Default")
      (node (ref "U$6") (pin "P$2") (pinfunction "NC_P$2") (pintype "bidirectional"))
    )
    (net (code "134") (name "unconnected-(U$7-P2.3_SPI-CS2-PadP2.4_SPI-CS2)") (class "Default")
      (node (ref "U$7") (pin "P2.4_SPI-CS2") (pinfunction "P2.3_SPI-CS2_P2.4_SPI-CS2") (pintype "bidirectional"))
    )
    (net (code "135") (name "unconnected-(U$7-PadP1.0_A0)") (class "Default")
      (node (ref "U$7") (pin "P1.0_A0") (pinfunction "P1.0_A0_P1.0_A0") (pintype "bidirectional"))
    )
    (net (code "136") (name "unconnected-(U$7-PadP1.1_A1)") (class "Default")
      (node (ref "U$7") (pin "P1.1_A1") (pinfunction "P1.1_A1_P1.1_A1") (pintype "bidirectional"))
    )
    (net (code "137") (name "unconnected-(U$7-PadP1.2_A2)") (class "Default")
      (node (ref "U$7") (pin "P1.2_A2") (pinfunction "P1.2_A2_P1.2_A2") (pintype "bidirectional"))
    )
    (net (code "138") (name "unconnected-(U$7-PadP1.3_A3)") (class "Default")
      (node (ref "U$7") (pin "P1.3_A3") (pinfunction "P1.3_A3_P1.3_A3") (pintype "bidirectional"))
    )
    (net (code "139") (name "unconnected-(U$7-PadP1.4_A4)") (class "Default")
      (node (ref "U$7") (pin "P1.4_A4") (pinfunction "P1.4_A4_P1.4_A4") (pintype "bidirectional"))
    )
    (net (code "140") (name "unconnected-(U$7-PadP1.5_A5)") (class "Default")
      (node (ref "U$7") (pin "P1.5_A5") (pinfunction "P1.5_A5_P1.5_A5") (pintype "bidirectional"))
    )
    (net (code "141") (name "unconnected-(U$7-PadP2.5_GPIO)") (class "Default")
      (node (ref "U$7") (pin "P2.5_GPIO") (pinfunction "P2.5_GPIO_P2.5_GPIO") (pintype "bidirectional"))
    )
    (net (code "142") (name "unconnected-(U$7-PadP2.7_SPI-CS3)") (class "Default")
      (node (ref "U$7") (pin "P2.7_SPI-CS3") (pinfunction "P2.7_SPI-CS3_P2.7_SPI-CS3") (pintype "bidirectional"))
    )
    (net (code "143") (name "unconnected-(U$7-PadP3.0_A12)") (class "Default")
      (node (ref "U$7") (pin "P3.0_A12") (pinfunction "P3.0_A12_P3.0_A12") (pintype "bidirectional"))
    )
    (net (code "144") (name "unconnected-(U$7-PadP3.1_A13)") (class "Default")
      (node (ref "U$7") (pin "P3.1_A13") (pinfunction "P3.1_A13_P3.1_A13") (pintype "bidirectional"))
    )
    (net (code "145") (name "unconnected-(U$7-PadP3.2_A14)") (class "Default")
      (node (ref "U$7") (pin "P3.2_A14") (pinfunction "P3.2_A14_P3.2_A14") (pintype "bidirectional"))
    )
    (net (code "146") (name "unconnected-(U$7-PadP3.3_A15)") (class "Default")
      (node (ref "U$7") (pin "P3.3_A15") (pinfunction "P3.3_A15_P3.3_A15") (pintype "bidirectional"))
    )
    (net (code "147") (name "unconnected-(U$7-PadP4.0_GPIO)") (class "Default")
      (node (ref "U$7") (pin "P4.0_GPIO") (pinfunction "P4.0_GPIO_P4.0_GPIO") (pintype "bidirectional"))
    )
    (net (code "148") (name "unconnected-(U$7-PadP4.1_GPIO)") (class "Default")
      (node (ref "U$7") (pin "P4.1_GPIO") (pinfunction "P4.1_GPIO_P4.1_GPIO") (pintype "bidirectional"))
    )
    (net (code "149") (name "unconnected-(U$7-PadP4.2_GPIO)") (class "Default")
      (node (ref "U$7") (pin "P4.2_GPIO") (pinfunction "P4.2_GPIO_P4.2_GPIO") (pintype "bidirectional"))
    )
    (net (code "150") (name "unconnected-(U$7-PadP4.3_GPIO)") (class "Default")
      (node (ref "U$7") (pin "P4.3_GPIO") (pinfunction "P4.3_GPIO_P4.3_GPIO") (pintype "bidirectional"))
    )
    (net (code "151") (name "unconnected-(U$7-PadP5.0_I2C-SDA-1)") (class "Default")
      (node (ref "U$7") (pin "P5.0_I2C-SDA-1") (pinfunction "P5.0_I2C-SDA-1_P5.0_I2C-SDA-1") (pintype "bidirectional"))
    )
    (net (code "152") (name "unconnected-(U$7-PadP5.1_I2C-SCL-1)") (class "Default")
      (node (ref "U$7") (pin "P5.1_I2C-SCL-1") (pinfunction "P5.1_I2C-SCL-1_P5.1_I2C-SCL-1") (pintype "bidirectional"))
    )
    (net (code "153") (name "unconnected-(U$7-PadP5.4_SPI-MOSI)") (class "Default")
      (node (ref "U$7") (pin "P5.4_SPI-MOSI") (pinfunction "P5.4_SPI-MOSI_P5.4_SPI-MOSI") (pintype "bidirectional"))
    )
    (net (code "154") (name "unconnected-(U$7-PadP5.5_SPI-MISO)") (class "Default")
      (node (ref "U$7") (pin "P5.5_SPI-MISO") (pinfunction "P5.5_SPI-MISO_P5.5_SPI-MISO") (pintype "bidirectional"))
    )
    (net (code "155") (name "unconnected-(U$7-PadP5.6_SPI-CLK)") (class "Default")
      (node (ref "U$7") (pin "P5.6_SPI-CLK") (pinfunction "P5.6_SPI-CLK_P5.6_SPI-CLK") (pintype "bidirectional"))
    )
    (net (code "156") (name "unconnected-(U$7-PadP7.0_I2C-SDA-2)") (class "Default")
      (node (ref "U$7") (pin "P7.0_I2C-SDA-2") (pinfunction "P7.0_I2C-SDA-2_P7.0_I2C-SDA-2") (pintype "bidirectional"))
    )
    (net (code "157") (name "unconnected-(U$7-PadP7.1_I2C-SCL-2)") (class "Default")
      (node (ref "U$7") (pin "P7.1_I2C-SCL-2") (pinfunction "P7.1_I2C-SCL-2_P7.1_I2C-SCL-2") (pintype "bidirectional"))
    )
    (net (code "158") (name "unconnected-(U$7-PadP7.3_GPIO)") (class "Default")
      (node (ref "U$7") (pin "P7.3_GPIO") (pinfunction "P7.3_GPIO_P7.3_GPIO") (pintype "bidirectional"))
    )
    (net (code "159") (name "unconnected-(U$7-PadP7.4_GPIO)") (class "Default")
      (node (ref "U$7") (pin "P7.4_GPIO") (pinfunction "P7.4_GPIO_P7.4_GPIO") (pintype "bidirectional"))
    )
  )
)
